# Sheet1.net
KiCad netlist of a schematic drawn in Altium Designer
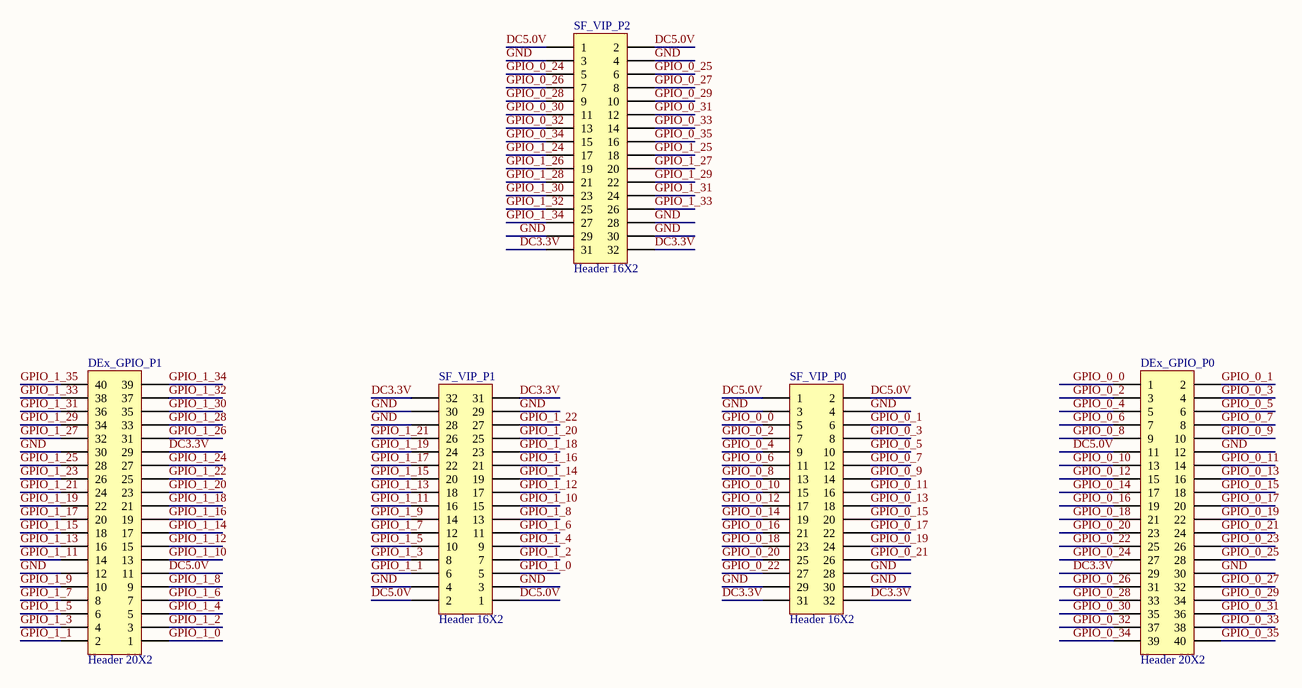
[diagram p0: Sheet1.SchDoc]

(export (version "E")
  (design (tool "Eeschema 10.0.6"))
  (components
    (comp (ref "DEx_GPIO_P0")
      (value "Header 20X2")
      (footprint "HDR2X20")
      (description "Header, 20-Pin, Dual row")
      (fields (field (name "PUBLISHER") "Altium Limited"))
      (libsource (lib "Miscellaneous Connectors") (part "Header 20X2"))
    )
    (comp (ref "DEx_GPIO_P1")
      (value "Header 20X2")
      (footprint "HDR2X20")
      (description "Header, 20-Pin, Dual row")
      (fields (field (name "PUBLISHER") "Altium Limited"))
      (libsource (lib "") (part "Header 20X2_1"))
    )
    (comp (ref "SF_VIP_P0")
      (value "Header 16X2")
      (footprint "HDR2X16")
      (description "Header, 16-Pin, Dual row")
      (fields (field (name "PUBLISHER") "Altium Limited"))
      (libsource (lib "") (part "Header 16X2_1"))
    )
    (comp (ref "SF_VIP_P1")
      (value "Header 16X2")
      (footprint "HDR2X16")
      (description "Header, 16-Pin, Dual row")
      (fields (field (name "PUBLISHER") "Altium Limited"))
      (libsource (lib "Miscellaneous Connectors") (part "Header 16X2"))
    )
    (comp (ref "SF_VIP_P2")
      (value "Header 16X2")
      (footprint "HDR2X16")
      (description "Header, 16-Pin, Dual row")
      (fields (field (name "PUBLISHER") "Altium Limited"))
      (libsource (lib "") (part "Header 16X2_1"))
    )
  )
  (nets
    (net (code "1") (name "/DC3.3V") (class "Default")
      (node (ref "DEx_GPIO_P0") (pin "29") (pinfunction "29_29") (pintype "passive"))
      (node (ref "DEx_GPIO_P1") (pin "29") (pinfunction "29_29") (pintype "passive"))
      (node (ref "SF_VIP_P0") (pin "31") (pinfunction "31_31") (pintype "passive"))
      (node (ref "SF_VIP_P0") (pin "32") (pinfunction "32_32") (pintype "passive"))
      (node (ref "SF_VIP_P1") (pin "31") (pinfunction "31_31") (pintype "passive"))
      (node (ref "SF_VIP_P1") (pin "32") (pinfunction "32_32") (pintype "passive"))
      (node (ref "SF_VIP_P2") (pin "31") (pinfunction "31_31") (pintype "passive"))
      (node (ref "SF_VIP_P2") (pin "32") (pinfunction "32_32") (pintype "passive"))
    )
    (net (code "2") (name "/DC5.0V") (class "Default")
      (node (ref "DEx_GPIO_P0") (pin "11") (pinfunction "11_11") (pintype "passive"))
      (node (ref "DEx_GPIO_P1") (pin "11") (pinfunction "11_11") (pintype "passive"))
      (node (ref "SF_VIP_P0") (pin "1") (pinfunction "1_1") (pintype "passive"))
      (node (ref "SF_VIP_P0") (pin "2") (pinfunction "2_2") (pintype "passive"))
      (node (ref "SF_VIP_P1") (pin "1") (pinfunction "1_1") (pintype "passive"))
      (node (ref "SF_VIP_P1") (pin "2") (pinfunction "2_2") (pintype "passive"))
      (node (ref "SF_VIP_P2") (pin "1") (pinfunction "1_1") (pintype "passive"))
      (node (ref "SF_VIP_P2") (pin "2") (pinfunction "2_2") (pintype "passive"))
    )
    (net (code "3") (name "/GND") (class "Default")
      (node (ref "DEx_GPIO_P0") (pin "12") (pinfunction "12_12") (pintype "passive"))
      (node (ref "DEx_GPIO_P0") (pin "30") (pinfunction "30_30") (pintype "passive"))
      (node (ref "DEx_GPIO_P1") (pin "12") (pinfunction "12_12") (pintype "passive"))
      (node (ref "DEx_GPIO_P1") (pin "30") (pinfunction "30_30") (pintype "passive"))
      (node (ref "SF_VIP_P0") (pin "28") (pinfunction "28_28") (pintype "passive"))
      (node (ref "SF_VIP_P0") (pin "29") (pinfunction "29_29") (pintype "passive"))
      (node (ref "SF_VIP_P0") (pin "3") (pinfunction "3_3") (pintype "passive"))
      (node (ref "SF_VIP_P0") (pin "30") (pinfunction "30_30") (pintype "passive"))
      (node (ref "SF_VIP_P0") (pin "4") (pinfunction "4_4") (pintype "passive"))
      (node (ref "SF_VIP_P1") (pin "28") (pinfunction "28_28") (pintype "passive"))
      (node (ref "SF_VIP_P1") (pin "29") (pinfunction "29_29") (pintype "passive"))
      (node (ref "SF_VIP_P1") (pin "3") (pinfunction "3_3") (pintype "passive"))
      (node (ref "SF_VIP_P1") (pin "30") (pinfunction "30_30") (pintype "passive"))
      (node (ref "SF_VIP_P1") (pin "4") (pinfunction "4_4") (pintype "passive"))
      (node (ref "SF_VIP_P2") (pin "28") (pinfunction "28_28") (pintype "passive"))
      (node (ref "SF_VIP_P2") (pin "29") (pinfunction "29_29") (pintype "passive"))
      (node (ref "SF_VIP_P2") (pin "3") (pinfunction "3_3") (pintype "passive"))
      (node (ref "SF_VIP_P2") (pin "30") (pinfunction "30_30") (pintype "passive"))
      (node (ref "SF_VIP_P2") (pin "4") (pinfunction "4_4") (pintype "passive"))
    )
    (net (code "4") (name "/GPIO_0_0") (class "Default")
      (node (ref "DEx_GPIO_P0") (pin "1") (pinfunction "1_1") (pintype "passive"))
      (node (ref "SF_VIP_P0") (pin "5") (pinfunction "5_5") (pintype "passive"))
    )
    (net (code "5") (name "/GPIO_0_1") (class "Default")
      (node (ref "DEx_GPIO_P0") (pin "2") (pinfunction "2_2") (pintype "passive"))
      (node (ref "SF_VIP_P0") (pin "6") (pinfunction "6_6") (pintype "passive"))
    )
    (net (code "6") (name "/GPIO_0_2") (class "Default")
      (node (ref "DEx_GPIO_P0") (pin "3") (pinfunction "3_3") (pintype "passive"))
      (node (ref "SF_VIP_P0") (pin "7") (pinfunction "7_7") (pintype "passive"))
    )
    (net (code "7") (name "/GPIO_0_3") (class "Default")
      (node (ref "DEx_GPIO_P0") (pin "4") (pinfunction "4_4") (pintype "passive"))
      (node (ref "SF_VIP_P0") (pin "8") (pinfunction "8_8") (pintype "passive"))
    )
    (net (code "8") (name "/GPIO_0_4") (class "Default")
      (node (ref "DEx_GPIO_P0") (pin "5") (pinfunction "5_5") (pintype "passive"))
      (node (ref "SF_VIP_P0") (pin "9") (pinfunction "9_9") (pintype "passive"))
    )
    (net (code "9") (name "/GPIO_0_5") (class "Default")
      (node (ref "DEx_GPIO_P0") (pin "6") (pinfunction "6_6") (pintype "passive"))
      (node (ref "SF_VIP_P0") (pin "10") (pinfunction "10_10") (pintype "passive"))
    )
    (net (code "10") (name "/GPIO_0_6") (class "Default")
      (node (ref "DEx_GPIO_P0") (pin "7") (pinfunction "7_7") (pintype "passive"))
      (node (ref "SF_VIP_P0") (pin "11") (pinfunction "11_11") (pintype "passive"))
    )
    (net (code "11") (name "/GPIO_0_7") (class "Default")
      (node (ref "DEx_GPIO_P0") (pin "8") (pinfunction "8_8") (pintype "passive"))
      (node (ref "SF_VIP_P0") (pin "12") (pinfunction "12_12") (pintype "passive"))
    )
    (net (code "12") (name "/GPIO_0_8") (class "Default")
      (node (ref "DEx_GPIO_P0") (pin "9") (pinfunction "9_9") (pintype "passive"))
      (node (ref "SF_VIP_P0") (pin "13") (pinfunction "13_13") (pintype "passive"))
    )
    (net (code "13") (name "/GPIO_0_9") (class "Default")
      (node (ref "DEx_GPIO_P0") (pin "10") (pinfunction "10_10") (pintype "passive"))
      (node (ref "SF_VIP_P0") (pin "14") (pinfunction "14_14") (pintype "passive"))
    )
    (net (code "14") (name "/GPIO_0_10") (class "Default")
      (node (ref "DEx_GPIO_P0") (pin "13") (pinfunction "13_13") (pintype "passive"))
      (node (ref "SF_VIP_P0") (pin "15") (pinfunction "15_15") (pintype "passive"))
    )
    (net (code "15") (name "/GPIO_0_11") (class "Default")
      (node (ref "DEx_GPIO_P0") (pin "14") (pinfunction "14_14") (pintype "passive"))
      (node (ref "SF_VIP_P0") (pin "16") (pinfunction "16_16") (pintype "passive"))
    )
    (net (code "16") (name "/GPIO_0_12") (class "Default")
      (node (ref "DEx_GPIO_P0") (pin "15") (pinfunction "15_15") (pintype "passive"))
      (node (ref "SF_VIP_P0") (pin "17") (pinfunction "17_17") (pintype "passive"))
    )
    (net (code "17") (name "/GPIO_0_13") (class "Default")
      (node (ref "DEx_GPIO_P0") (pin "16") (pinfunction "16_16") (pintype "passive"))
      (node (ref "SF_VIP_P0") (pin "18") (pinfunction "18_18") (pintype "passive"))
    )
    (net (code "18") (name "/GPIO_0_14") (class "Default")
      (node (ref "DEx_GPIO_P0") (pin "17") (pinfunction "17_17") (pintype "passive"))
      (node (ref "SF_VIP_P0") (pin "19") (pinfunction "19_19") (pintype "passive"))
    )
    (net (code "19") (name "/GPIO_0_15") (class "Default")
      (node (ref "DEx_GPIO_P0") (pin "18") (pinfunction "18_18") (pintype "passive"))
      (node (ref "SF_VIP_P0") (pin "20") (pinfunction "20_20") (pintype "passive"))
    )
    (net (code "20") (name "/GPIO_0_16") (class "Default")
      (node (ref "DEx_GPIO_P0") (pin "19") (pinfunction "19_19") (pintype "passive"))
      (node (ref "SF_VIP_P0") (pin "21") (pinfunction "21_21") (pintype "passive"))
    )
    (net (code "21") (name "/GPIO_0_17") (class "Default")
      (node (ref "DEx_GPIO_P0") (pin "20") (pinfunction "20_20") (pintype "passive"))
      (node (ref "SF_VIP_P0") (pin "22") (pinfunction "22_22") (pintype "passive"))
    )
    (net (code "22") (name "/GPIO_0_18") (class "Default")
      (node (ref "DEx_GPIO_P0") (pin "21") (pinfunction "21_21") (pintype "passive"))
      (node (ref "SF_VIP_P0") (pin "23") (pinfunction "23_23") (pintype "passive"))
    )
    (net (code "23") (name "/GPIO_0_19") (class "Default")
      (node (ref "DEx_GPIO_P0") (pin "22") (pinfunction "22_22") (pintype "passive"))
      (node (ref "SF_VIP_P0") (pin "24") (pinfunction "24_24") (pintype "passive"))
    )
    (net (code "24") (name "/GPIO_0_20") (class "Default")
      (node (ref "DEx_GPIO_P0") (pin "23") (pinfunction "23_23") (pintype "passive"))
      (node (ref "SF_VIP_P0") (pin "25") (pinfunction "25_25") (pintype "passive"))
    )
    (net (code "25") (name "/GPIO_0_21") (class "Default")
      (node (ref "DEx_GPIO_P0") (pin "24") (pinfunction "24_24") (pintype "passive"))
      (node (ref "SF_VIP_P0") (pin "26") (pinfunction "26_26") (pintype "passive"))
    )
    (net (code "26") (name "/GPIO_0_22") (class "Default")
      (node (ref "DEx_GPIO_P0") (pin "25") (pinfunction "25_25") (pintype "passive"))
      (node (ref "SF_VIP_P0") (pin "27") (pinfunction "27_27") (pintype "passive"))
    )
    (net (code "27") (name "/GPIO_0_23") (class "Default")
      (node (ref "DEx_GPIO_P0") (pin "26") (pinfunction "26_26") (pintype "passive"))
    )
    (net (code "28") (name "/GPIO_0_24") (class "Default")
      (node (ref "DEx_GPIO_P0") (pin "27") (pinfunction "27_27") (pintype "passive"))
      (node (ref "SF_VIP_P2") (pin "5") (pinfunction "5_5") (pintype "passive"))
    )
    (net (code "29") (name "/GPIO_0_25") (class "Default")
      (node (ref "DEx_GPIO_P0") (pin "28") (pinfunction "28_28") (pintype "passive"))
      (node (ref "SF_VIP_P2") (pin "6") (pinfunction "6_6") (pintype "passive"))
    )
    (net (code "30") (name "/GPIO_0_26") (class "Default")
      (node (ref "DEx_GPIO_P0") (pin "31") (pinfunction "31_31") (pintype "passive"))
      (node (ref "SF_VIP_P2") (pin "7") (pinfunction "7_7") (pintype "passive"))
    )
    (net (code "31") (name "/GPIO_0_27") (class "Default")
      (node (ref "DEx_GPIO_P0") (pin "32") (pinfunction "32_32") (pintype "passive"))
      (node (ref "SF_VIP_P2") (pin "8") (pinfunction "8_8") (pintype "passive"))
    )
    (net (code "32") (name "/GPIO_0_28") (class "Default")
      (node (ref "DEx_GPIO_P0") (pin "33") (pinfunction "33_33") (pintype "passive"))
      (node (ref "SF_VIP_P2") (pin "9") (pinfunction "9_9") (pintype "passive"))
    )
    (net (code "33") (name "/GPIO_0_29") (class "Default")
      (node (ref "DEx_GPIO_P0") (pin "34") (pinfunction "34_34") (pintype "passive"))
      (node (ref "SF_VIP_P2") (pin "10") (pinfunction "10_10") (pintype "passive"))
    )
    (net (code "34") (name "/GPIO_0_30") (class "Default")
      (node (ref "DEx_GPIO_P0") (pin "35") (pinfunction "35_35") (pintype "passive"))
      (node (ref "SF_VIP_P2") (pin "11") (pinfunction "11_11") (pintype "passive"))
    )
    (net (code "35") (name "/GPIO_0_31") (class "Default")
      (node (ref "DEx_GPIO_P0") (pin "36") (pinfunction "36_36") (pintype "passive"))
      (node (ref "SF_VIP_P2") (pin "12") (pinfunction "12_12") (pintype "passive"))
    )
    (net (code "36") (name "/GPIO_0_32") (class "Default")
      (node (ref "DEx_GPIO_P0") (pin "37") (pinfunction "37_37") (pintype "passive"))
      (node (ref "SF_VIP_P2") (pin "13") (pinfunction "13_13") (pintype "passive"))
    )
    (net (code "37") (name "/GPIO_0_33") (class "Default")
      (node (ref "DEx_GPIO_P0") (pin "38") (pinfunction "38_38") (pintype "passive"))
      (node (ref "SF_VIP_P2") (pin "14") (pinfunction "14_14") (pintype "passive"))
    )
    (net (code "38") (name "/GPIO_0_34") (class "Default")
      (node (ref "DEx_GPIO_P0") (pin "39") (pinfunction "39_39") (pintype "passive"))
      (node (ref "SF_VIP_P2") (pin "15") (pinfunction "15_15") (pintype "passive"))
    )
    (net (code "39") (name "/GPIO_0_35") (class "Default")
      (node (ref "DEx_GPIO_P0") (pin "40") (pinfunction "40_40") (pintype "passive"))
      (node (ref "SF_VIP_P2") (pin "16") (pinfunction "16_16") (pintype "passive"))
    )
    (net (code "40") (name "/GPIO_1_0") (class "Default")
      (node (ref "DEx_GPIO_P1") (pin "1") (pinfunction "1_1") (pintype "passive"))
      (node (ref "SF_VIP_P1") (pin "5") (pinfunction "5_5") (pintype "passive"))
    )
    (net (code "41") (name "/GPIO_1_1") (class "Default")
      (node (ref "DEx_GPIO_P1") (pin "2") (pinfunction "2_2") (pintype "passive"))
      (node (ref "SF_VIP_P1") (pin "6") (pinfunction "6_6") (pintype "passive"))
    )
    (net (code "42") (name "/GPIO_1_2") (class "Default")
      (node (ref "DEx_GPIO_P1") (pin "3") (pinfunction "3_3") (pintype "passive"))
      (node (ref "SF_VIP_P1") (pin "7") (pinfunction "7_7") (pintype "passive"))
    )
    (net (code "43") (name "/GPIO_1_3") (class "Default")
      (node (ref "DEx_GPIO_P1") (pin "4") (pinfunction "4_4") (pintype "passive"))
      (node (ref "SF_VIP_P1") (pin "8") (pinfunction "8_8") (pintype "passive"))
    )
    (net (code "44") (name "/GPIO_1_4") (class "Default")
      (node (ref "DEx_GPIO_P1") (pin "5") (pinfunction "5_5") (pintype "passive"))
      (node (ref "SF_VIP_P1") (pin "9") (pinfunction "9_9") (pintype "passive"))
    )
    (net (code "45") (name "/GPIO_1_5") (class "Default")
      (node (ref "DEx_GPIO_P1") (pin "6") (pinfunction "6_6") (pintype "passive"))
      (node (ref "SF_VIP_P1") (pin "10") (pinfunction "10_10") (pintype "passive"))
    )
    (net (code "46") (name "/GPIO_1_6") (class "Default")
      (node (ref "DEx_GPIO_P1") (pin "7") (pinfunction "7_7") (pintype "passive"))
      (node (ref "SF_VIP_P1") (pin "11") (pinfunction "11_11") (pintype "passive"))
    )
    (net (code "47") (name "/GPIO_1_7") (class "Default")
      (node (ref "DEx_GPIO_P1") (pin "8") (pinfunction "8_8") (pintype "passive"))
      (node (ref "SF_VIP_P1") (pin "12") (pinfunction "12_12") (pintype "passive"))
    )
    (net (code "48") (name "/GPIO_1_8") (class "Default")
      (node (ref "DEx_GPIO_P1") (pin "9") (pinfunction "9_9") (pintype "passive"))
      (node (ref "SF_VIP_P1") (pin "13") (pinfunction "13_13") (pintype "passive"))
    )
    (net (code "49") (name "/GPIO_1_9") (class "Default")
      (node (ref "DEx_GPIO_P1") (pin "10") (pinfunction "10_10") (pintype "passive"))
      (node (ref "SF_VIP_P1") (pin "14") (pinfunction "14_14") (pintype "passive"))
    )
    (net (code "50") (name "/GPIO_1_10") (class "Default")
      (node (ref "DEx_GPIO_P1") (pin "13") (pinfunction "13_13") (pintype "passive"))
      (node (ref "SF_VIP_P1") (pin "15") (pinfunction "15_15") (pintype "passive"))
    )
    (net (code "51") (name "/GPIO_1_11") (class "Default")
      (node (ref "DEx_GPIO_P1") (pin "14") (pinfunction "14_14") (pintype "passive"))
      (node (ref "SF_VIP_P1") (pin "16") (pinfunction "16_16") (pintype "passive"))
    )
    (net (code "52") (name "/GPIO_1_12") (class "Default")
      (node (ref "DEx_GPIO_P1") (pin "15") (pinfunction "15_15") (pintype "passive"))
      (node (ref "SF_VIP_P1") (pin "17") (pinfunction "17_17") (pintype "passive"))
    )
    (net (code "53") (name "/GPIO_1_13") (class "Default")
      (node (ref "DEx_GPIO_P1") (pin "16") (pinfunction "16_16") (pintype "passive"))
      (node (ref "SF_VIP_P1") (pin "18") (pinfunction "18_18") (pintype "passive"))
    )
    (net (code "54") (name "/GPIO_1_14") (class "Default")
      (node (ref "DEx_GPIO_P1") (pin "17") (pinfunction "17_17") (pintype "passive"))
      (node (ref "SF_VIP_P1") (pin "19") (pinfunction "19_19") (pintype "passive"))
    )
    (net (code "55") (name "/GPIO_1_15") (class "Default")
      (node (ref "DEx_GPIO_P1") (pin "18") (pinfunction "18_18") (pintype "passive"))
      (node (ref "SF_VIP_P1") (pin "20") (pinfunction "20_20") (pintype "passive"))
    )
    (net (code "56") (name "/GPIO_1_16") (class "Default")
      (node (ref "DEx_GPIO_P1") (pin "19") (pinfunction "19_19") (pintype "passive"))
      (node (ref "SF_VIP_P1") (pin "21") (pinfunction "21_21") (pintype "passive"))
    )
    (net (code "57") (name "/GPIO_1_17") (class "Default")
      (node (ref "DEx_GPIO_P1") (pin "20") (pinfunction "20_20") (pintype "passive"))
      (node (ref "SF_VIP_P1") (pin "22") (pinfunction "22_22") (pintype "passive"))
    )
    (net (code "58") (name "/GPIO_1_18") (class "Default")
      (node (ref "DEx_GPIO_P1") (pin "21") (pinfunction "21_21") (pintype "passive"))
      (node (ref "SF_VIP_P1") (pin "23") (pinfunction "23_23") (pintype "passive"))
    )
    (net (code "59") (name "/GPIO_1_19") (class "Default")
      (node (ref "DEx_GPIO_P1") (pin "22") (pinfunction "22_22") (pintype "passive"))
      (node (ref "SF_VIP_P1") (pin "24") (pinfunction "24_24") (pintype "passive"))
    )
    (net (code "60") (name "/GPIO_1_20") (class "Default")
      (node (ref "DEx_GPIO_P1") (pin "23") (pinfunction "23_23") (pintype "passive"))
      (node (ref "SF_VIP_P1") (pin "25") (pinfunction "25_25") (pintype "passive"))
    )
    (net (code "61") (name "/GPIO_1_21") (class "Default")
      (node (ref "DEx_GPIO_P1") (pin "24") (pinfunction "24_24") (pintype "passive"))
      (node (ref "SF_VIP_P1") (pin "26") (pinfunction "26_26") (pintype "passive"))
    )
    (net (code "62") (name "/GPIO_1_22") (class "Default")
      (node (ref "DEx_GPIO_P1") (pin "25") (pinfunction "25_25") (pintype "passive"))
      (node (ref "SF_VIP_P1") (pin "27") (pinfunction "27_27") (pintype "passive"))
    )
    (net (code "63") (name "/GPIO_1_23") (class "Default")
      (node (ref "DEx_GPIO_P1") (pin "26") (pinfunction "26_26") (pintype "passive"))
    )
    (net (code "64") (name "/GPIO_1_24") (class "Default")
      (node (ref "DEx_GPIO_P1") (pin "27") (pinfunction "27_27") (pintype "passive"))
      (node (ref "SF_VIP_P2") (pin "17") (pinfunction "17_17") (pintype "passive"))
    )
    (net (code "65") (name "/GPIO_1_25") (class "Default")
      (node (ref "DEx_GPIO_P1") (pin "28") (pinfunction "28_28") (pintype "passive"))
      (node (ref "SF_VIP_P2") (pin "18") (pinfunction "18_18") (pintype "passive"))
    )
    (net (code "66") (name "/GPIO_1_26") (class "Default")
      (node (ref "DEx_GPIO_P1") (pin "31") (pinfunction "31_31") (pintype "passive"))
      (node (ref "SF_VIP_P2") (pin "19") (pinfunction "19_19") (pintype "passive"))
    )
    (net (code "67") (name "/GPIO_1_27") (class "Default")
      (node (ref "DEx_GPIO_P1") (pin "32") (pinfunction "32_32") (pintype "passive"))
      (node (ref "SF_VIP_P2") (pin "20") (pinfunction "20_20") (pintype "passive"))
    )
    (net (code "68") (name "/GPIO_1_28") (class "Default")
      (node (ref "DEx_GPIO_P1") (pin "33") (pinfunction "33_33") (pintype "passive"))
      (node (ref "SF_VIP_P2") (pin "21") (pinfunction "21_21") (pintype "passive"))
    )
    (net (code "69") (name "/GPIO_1_29") (class "Default")
      (node (ref "DEx_GPIO_P1") (pin "34") (pinfunction "34_34") (pintype "passive"))
      (node (ref "SF_VIP_P2") (pin "22") (pinfunction "22_22") (pintype "passive"))
    )
    (net (code "70") (name "/GPIO_1_30") (class "Default")
      (node (ref "DEx_GPIO_P1") (pin "35") (pinfunction "35_35") (pintype "passive"))
      (node (ref "SF_VIP_P2") (pin "23") (pinfunction "23_23") (pintype "passive"))
    )
    (net (code "71") (name "/GPIO_1_31") (class "Default")
      (node (ref "DEx_GPIO_P1") (pin "36") (pinfunction "36_36") (pintype "passive"))
      (node (ref "SF_VIP_P2") (pin "24") (pinfunction "24_24") (pintype "passive"))
    )
    (net (code "72") (name "/GPIO_1_32") (class "Default")
      (node (ref "DEx_GPIO_P1") (pin "37") (pinfunction "37_37") (pintype "passive"))
      (node (ref "SF_VIP_P2") (pin "25") (pinfunction "25_25") (pintype "passive"))
    )
    (net (code "73") (name "/GPIO_1_33") (class "Default")
      (node (ref "DEx_GPIO_P1") (pin "38") (pinfunction "38_38") (pintype "passive"))
      (node (ref "SF_VIP_P2") (pin "26") (pinfunction "26_26") (pintype "passive"))
    )
    (net (code "74") (name "/GPIO_1_34") (class "Default")
      (node (ref "DEx_GPIO_P1") (pin "39") (pinfunction "39_39") (pintype "passive"))
      (node (ref "SF_VIP_P2") (pin "27") (pinfunction "27_27") (pintype "passive"))
    )
    (net (code "75") (name "/GPIO_1_35") (class "Default")
      (node (ref "DEx_GPIO_P1") (pin "40") (pinfunction "40_40") (pintype "passive"))
    )
  )
)
